# nose_blink.net
KiCad netlist of a schematic drawn in Altium Designer
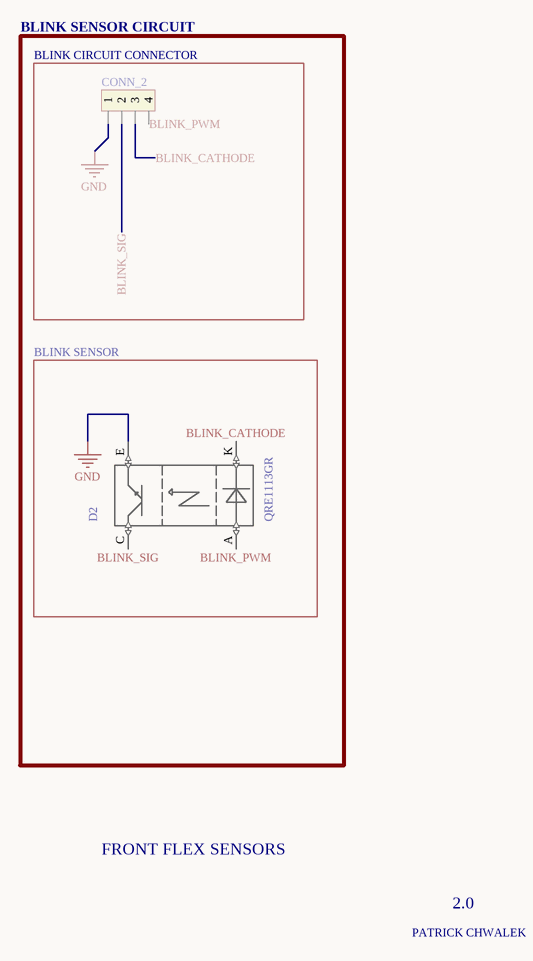
[diagram p0: nose_blink.SchDoc]

(export (version "E")
  (design (tool "Eeschema 10.0.6"))
  (components
    (comp (ref "CONN_2")
      (value "BLINK")
      (footprint "4_pos_1mm_header")
      (libsource (lib "schematic_components") (part "4_pin_1mm_header"))
    )
    (comp (ref "D2")
      (value "QRE1113GR")
      (footprint "*4LEADSMD_QRE1113GR(Primary)")
      (description "QRE1113 Series 30 V 50 mA Miniature Reflective Object Sensor - SMD-4")
      (fields (field (name "MF") "ON Semiconductor"))
      (libsource (lib "QRE1113GR") (part "QRE1113GR"))
    )
  )
  (nets
    (net (code "1") (name "/BLINK_CATHODE") (class "Default")
      (node (ref "CONN_2") (pin "3") (pinfunction "3_3") (pintype "passive"))
      (node (ref "D2") (pin "K") (pinfunction "K_K") (pintype "bidirectional"))
    )
    (net (code "2") (name "/BLINK_PWM") (class "Default")
      (node (ref "CONN_2") (pin "4") (pinfunction "4_4") (pintype "passive"))
      (node (ref "D2") (pin "A") (pinfunction "A_A") (pintype "bidirectional"))
    )
    (net (code "3") (name "/BLINK_SIG") (class "Default")
      (node (ref "CONN_2") (pin "2") (pinfunction "2_2") (pintype "passive"))
      (node (ref "D2") (pin "C") (pinfunction "C_C") (pintype "bidirectional"))
    )
    (net (code "4") (name "GND") (class "Default")
      (node (ref "CONN_2") (pin "1") (pinfunction "1_1") (pintype "passive"))
      (node (ref "D2") (pin "E") (pinfunction "E_E") (pintype "bidirectional"))
    )
  )
)
